# Carduino_328.net
KiCad netlist of a schematic drawn in EAGLE
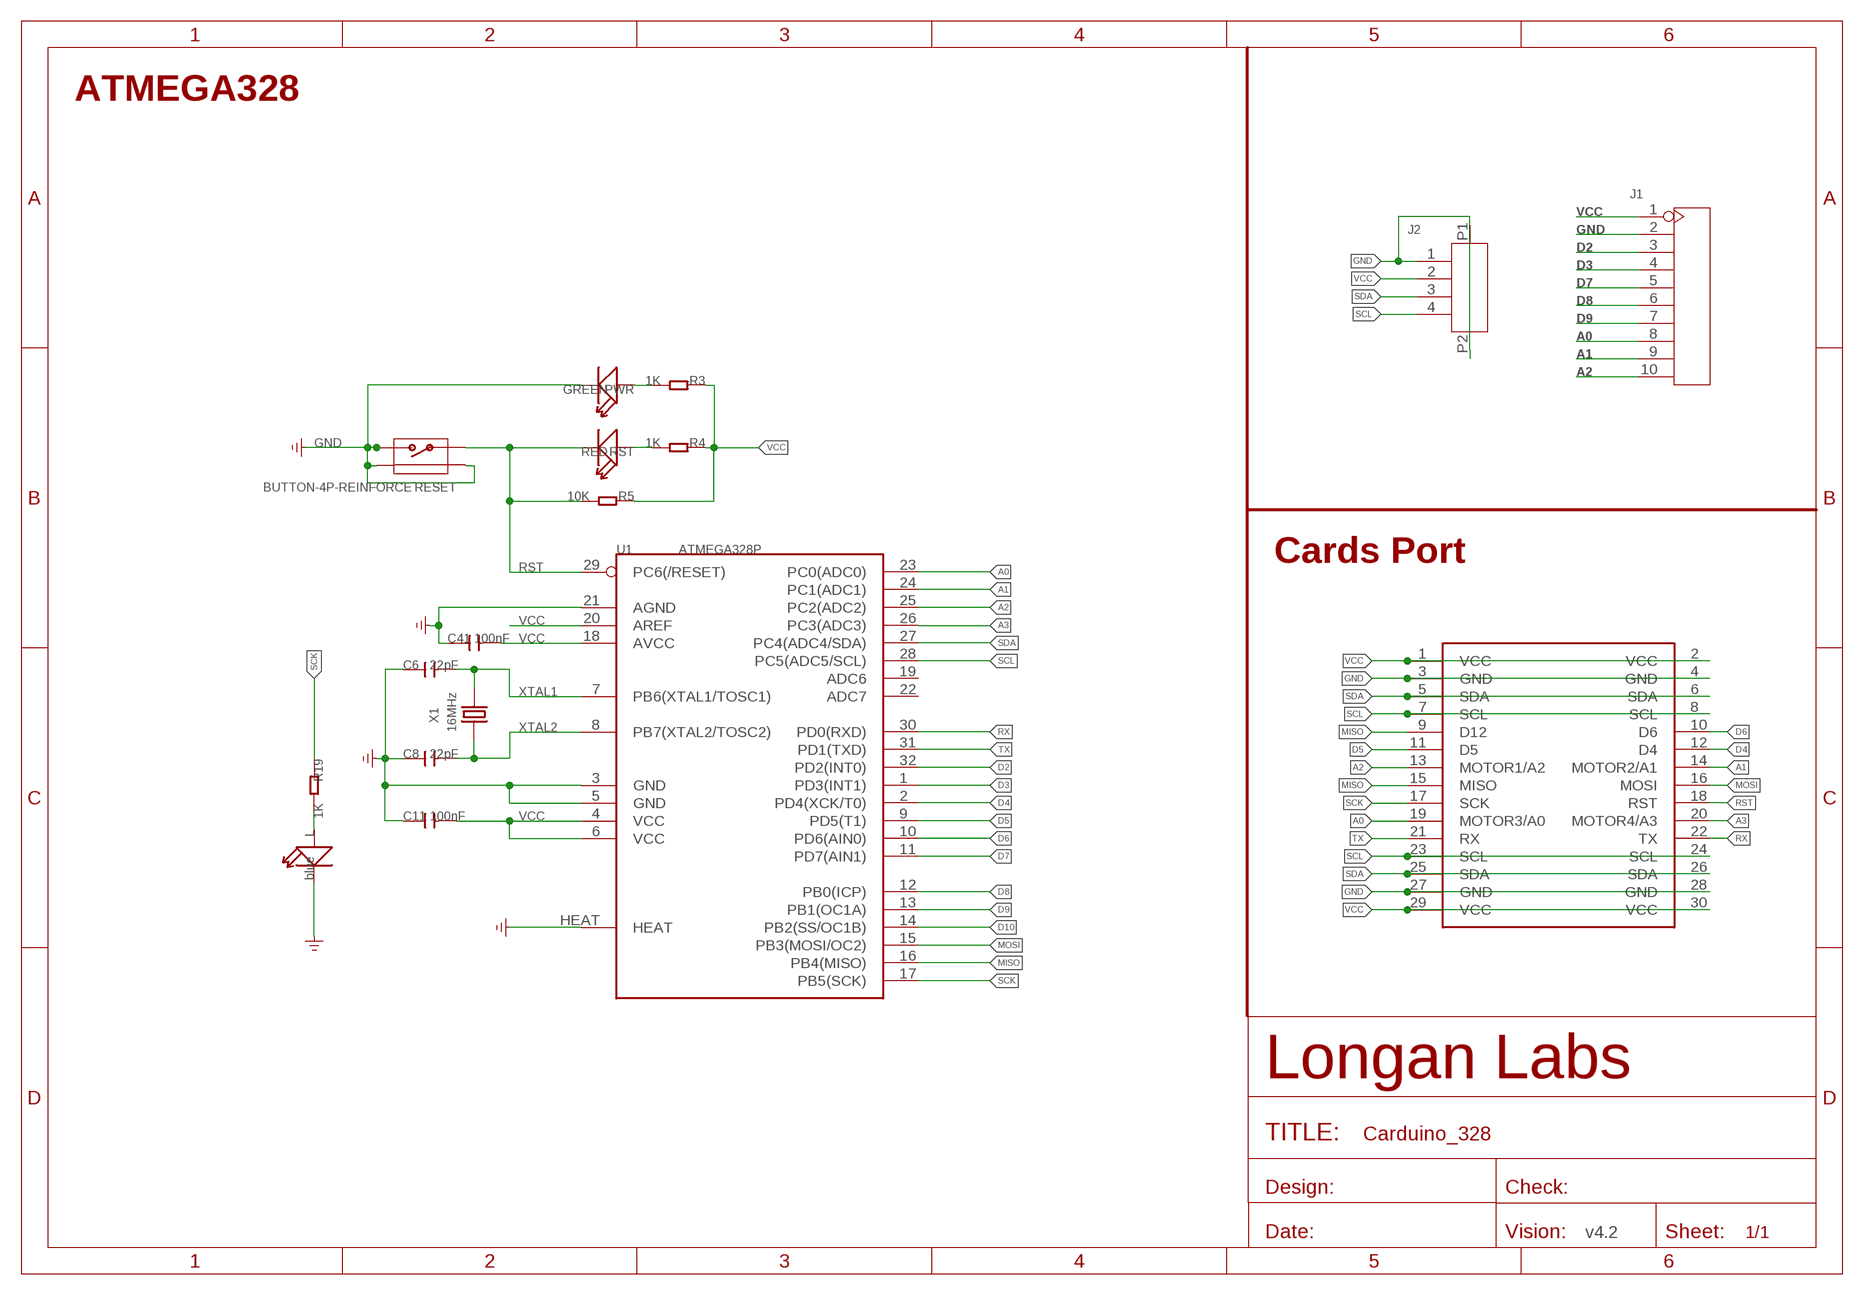
[diagram p0: schematic, sheet 1]

(export (version "E")
  (design (tool "Eeschema 10.0.6"))
  (components
    (comp (ref "C6")
      (value "22pF")
      (footprint "eagle-import:C0603")
      (libsource (lib "eagle-import") (part "C-0603"))
    )
    (comp (ref "C8")
      (value "22pF")
      (footprint "eagle-import:C0603")
      (libsource (lib "eagle-import") (part "C-0603"))
    )
    (comp (ref "C11")
      (value "100nF")
      (footprint "eagle-import:C0603")
      (libsource (lib "eagle-import") (part "C-0603"))
    )
    (comp (ref "C41")
      (value "100nF")
      (footprint "eagle-import:C0603")
      (libsource (lib "eagle-import") (part "C-0603"))
    )
    (comp (ref "J1")
      (value "HEADER-10P-2.54")
      (footprint "eagle-import:H10-2.54")
      (libsource (lib "eagle-import") (part "HEADER-10P-2.54"))
    )
    (comp (ref "J2")
      (value "HEADER-4P-1.0")
      (footprint "eagle-import:4P-1.0-90D")
      (libsource (lib "eagle-import") (part "HEADER-4P-1.0"))
    )
    (comp (ref "L")
      (value "blue")
      (footprint "eagle-import:LED-0603")
      (libsource (lib "eagle-import") (part "LED'0603'"))
    )
    (comp (ref "MOUDLE1")
      (value "MOUDLE-2X15P-MCU'BOARD'")
      (footprint "eagle-import:MOUDLE-2X15P-2.54")
      (libsource (lib "eagle-import") (part "MOUDLE-2X15P-MCU'BOARD'"))
    )
    (comp (ref "PWR")
      (value "GREEN")
      (footprint "eagle-import:LED-0603")
      (libsource (lib "eagle-import") (part "LED'0603'"))
    )
    (comp (ref "R3")
      (value "1K")
      (footprint "eagle-import:R0603")
      (libsource (lib "eagle-import") (part "R-0603"))
    )
    (comp (ref "R4")
      (value "1K")
      (footprint "eagle-import:R0603")
      (libsource (lib "eagle-import") (part "R-0603"))
    )
    (comp (ref "R5")
      (value "10K")
      (footprint "eagle-import:R0603")
      (libsource (lib "eagle-import") (part "R-0603"))
    )
    (comp (ref "R19")
      (value "1K")
      (footprint "eagle-import:R0603")
      (libsource (lib "eagle-import") (part "R-0603"))
    )
    (comp (ref "RESET")
      (value "BUTTON-4P-REINFORCE")
      (footprint "eagle-import:4P-SMD-7X3.5X3.5H")
      (libsource (lib "eagle-import") (part "BUTTON-4P-REINFORCE'TS-1188E'"))
    )
    (comp (ref "RST")
      (value "RED")
      (footprint "eagle-import:LED-0603")
      (libsource (lib "eagle-import") (part "LED'0603'"))
    )
    (comp (ref "U1")
      (value "ATMEGA328P")
      (footprint "eagle-import:MLF32X")
      (libsource (lib "eagle-import") (part "MEGA8"))
    )
    (comp (ref "X1")
      (value "16MHz")
      (footprint "eagle-import:2P-SMD-5X3.2")
      (libsource (lib "eagle-import") (part "CRYSTAL'5032'"))
    )
  )
  (nets
    (net (code "1") (name "/XTAL1") (class "Default")
      (node (ref "C6") (pin "2") (pinfunction "2_2") (pintype "passive"))
      (node (ref "U1") (pin "7") (pinfunction "PB6(XTAL1/TOSC1)_7") (pintype "bidirectional"))
      (node (ref "X1") (pin "2") (pinfunction "2_2") (pintype "passive"))
    )
    (net (code "2") (name "/XTAL2") (class "Default")
      (node (ref "C8") (pin "2") (pinfunction "2_2") (pintype "passive"))
      (node (ref "U1") (pin "8") (pinfunction "PB7(XTAL2/TOSC2)_8") (pintype "bidirectional"))
      (node (ref "X1") (pin "1") (pinfunction "1_1") (pintype "passive"))
    )
    (net (code "3") (name "A0") (class "Default")
      (node (ref "J1") (pin "8") (pinfunction "8_8") (pintype "bidirectional"))
      (node (ref "MOUDLE1") (pin "19") (pinfunction "MOTOR3/A0_19") (pintype "bidirectional"))
      (node (ref "U1") (pin "23") (pinfunction "PC0(ADC0)_23") (pintype "bidirectional"))
    )
    (net (code "4") (name "A1") (class "Default")
      (node (ref "J1") (pin "9") (pinfunction "9_9") (pintype "bidirectional"))
      (node (ref "MOUDLE1") (pin "14") (pinfunction "MOTOR2/A1_14") (pintype "bidirectional"))
      (node (ref "U1") (pin "24") (pinfunction "PC1(ADC1)_24") (pintype "bidirectional"))
    )
    (net (code "5") (name "A2") (class "Default")
      (node (ref "J1") (pin "10") (pinfunction "10_10") (pintype "bidirectional"))
      (node (ref "MOUDLE1") (pin "13") (pinfunction "MOTOR1/A2_13") (pintype "bidirectional"))
      (node (ref "U1") (pin "25") (pinfunction "PC2(ADC2)_25") (pintype "bidirectional"))
    )
    (net (code "6") (name "A3") (class "Default")
      (node (ref "MOUDLE1") (pin "20") (pinfunction "MOTOR4/A3_20") (pintype "bidirectional"))
      (node (ref "U1") (pin "26") (pinfunction "PC3(ADC3)_26") (pintype "bidirectional"))
    )
    (net (code "7") (name "D2") (class "Default")
      (node (ref "J1") (pin "3") (pinfunction "3_3") (pintype "bidirectional"))
      (node (ref "U1") (pin "32") (pinfunction "PD2(INT0)_32") (pintype "bidirectional"))
    )
    (net (code "8") (name "D3") (class "Default")
      (node (ref "J1") (pin "4") (pinfunction "4_4") (pintype "bidirectional"))
      (node (ref "U1") (pin "1") (pinfunction "PD3(INT1)_1") (pintype "bidirectional"))
    )
    (net (code "9") (name "D4") (class "Default")
      (node (ref "MOUDLE1") (pin "12") (pinfunction "D4_12") (pintype "bidirectional"))
      (node (ref "U1") (pin "2") (pinfunction "PD4(XCK/T0)_2") (pintype "bidirectional"))
    )
    (net (code "10") (name "D5") (class "Default")
      (node (ref "MOUDLE1") (pin "11") (pinfunction "D5_11") (pintype "bidirectional"))
      (node (ref "U1") (pin "9") (pinfunction "PD5(T1)_9") (pintype "bidirectional"))
    )
    (net (code "11") (name "D6") (class "Default")
      (node (ref "MOUDLE1") (pin "10") (pinfunction "D6_10") (pintype "bidirectional"))
      (node (ref "U1") (pin "10") (pinfunction "PD6(AIN0)_10") (pintype "bidirectional"))
    )
    (net (code "12") (name "D7") (class "Default")
      (node (ref "J1") (pin "5") (pinfunction "5_5") (pintype "bidirectional"))
      (node (ref "U1") (pin "11") (pinfunction "PD7(AIN1)_11") (pintype "bidirectional"))
    )
    (net (code "13") (name "D8") (class "Default")
      (node (ref "J1") (pin "6") (pinfunction "6_6") (pintype "bidirectional"))
      (node (ref "U1") (pin "12") (pinfunction "PB0(ICP)_12") (pintype "bidirectional"))
    )
    (net (code "14") (name "D9") (class "Default")
      (node (ref "J1") (pin "7") (pinfunction "7_7") (pintype "bidirectional"))
      (node (ref "U1") (pin "13") (pinfunction "PB1(OC1A)_13") (pintype "bidirectional"))
    )
    (net (code "15") (name "D10") (class "Default")
      (node (ref "U1") (pin "14") (pinfunction "PB2(SS/OC1B)_14") (pintype "bidirectional"))
    )
    (net (code "16") (name "GND") (class "Default")
      (node (ref "C11") (pin "1") (pinfunction "1_1") (pintype "passive"))
      (node (ref "C41") (pin "1") (pinfunction "1_1") (pintype "passive"))
      (node (ref "C6") (pin "1") (pinfunction "1_1") (pintype "passive"))
      (node (ref "C8") (pin "1") (pinfunction "1_1") (pintype "passive"))
      (node (ref "J1") (pin "2") (pinfunction "2_2") (pintype "bidirectional"))
      (node (ref "J2") (pin "1") (pinfunction "1_1") (pintype "bidirectional"))
      (node (ref "J2") (pin "P1") (pinfunction "P1_P1") (pintype "bidirectional"))
      (node (ref "J2") (pin "P2") (pinfunction "P2_P2") (pintype "bidirectional"))
      (node (ref "L") (pin "-") (pinfunction "-_-") (pintype "passive"))
      (node (ref "MOUDLE1") (pin "27") (pinfunction "GND_27") (pintype "bidirectional"))
      (node (ref "MOUDLE1") (pin "28") (pinfunction "GND_28") (pintype "bidirectional"))
      (node (ref "MOUDLE1") (pin "3") (pinfunction "GND_3") (pintype "bidirectional"))
      (node (ref "MOUDLE1") (pin "4") (pinfunction "GND_4") (pintype "bidirectional"))
      (node (ref "PWR") (pin "-") (pinfunction "-_-") (pintype "passive"))
      (node (ref "RESET") (pin "2") (pinfunction "2_2") (pintype "bidirectional"))
      (node (ref "RESET") (pin "S1") (pinfunction "S1_S1") (pintype "bidirectional"))
      (node (ref "RESET") (pin "S2") (pinfunction "S2_S2") (pintype "bidirectional"))
      (node (ref "U1") (pin "21") (pinfunction "AGND_21") (pintype "bidirectional"))
      (node (ref "U1") (pin "3") (pinfunction "GND_3") (pintype "bidirectional"))
      (node (ref "U1") (pin "5") (pinfunction "GND_5") (pintype "bidirectional"))
      (node (ref "U1") (pin "HEAT") (pinfunction "HEAT_HEAT") (pintype "bidirectional"))
    )
    (net (code "17") (name "MISO") (class "Default")
      (node (ref "MOUDLE1") (pin "15") (pinfunction "MISO_15") (pintype "bidirectional"))
      (node (ref "MOUDLE1") (pin "9") (pinfunction "D12_9") (pintype "bidirectional"))
      (node (ref "U1") (pin "16") (pinfunction "PB4(MISO)_16") (pintype "bidirectional"))
    )
    (net (code "18") (name "MOSI") (class "Default")
      (node (ref "MOUDLE1") (pin "16") (pinfunction "MOSI_16") (pintype "bidirectional"))
      (node (ref "U1") (pin "15") (pinfunction "PB3(MOSI/OC2)_15") (pintype "bidirectional"))
    )
    (net (code "19") (name "Net-(L-Pad+)") (class "Default")
      (node (ref "L") (pin "+") (pinfunction "+_+") (pintype "passive"))
      (node (ref "R19") (pin "2") (pinfunction "2_2") (pintype "passive"))
    )
    (net (code "20") (name "Net-(PWR-Pad+)") (class "Default")
      (node (ref "PWR") (pin "+") (pinfunction "+_+") (pintype "passive"))
      (node (ref "R3") (pin "2") (pinfunction "2_2") (pintype "passive"))
    )
    (net (code "21") (name "Net-(R4-Pad2)") (class "Default")
      (node (ref "R4") (pin "2") (pinfunction "2_2") (pintype "passive"))
      (node (ref "RST") (pin "+") (pinfunction "+_+") (pintype "passive"))
    )
    (net (code "22") (name "RST") (class "Default")
      (node (ref "MOUDLE1") (pin "18") (pinfunction "RST_18") (pintype "bidirectional"))
      (node (ref "R5") (pin "2") (pinfunction "2_2") (pintype "passive"))
      (node (ref "RESET") (pin "1") (pinfunction "1_1") (pintype "bidirectional"))
      (node (ref "RST") (pin "-") (pinfunction "-_-") (pintype "passive"))
      (node (ref "U1") (pin "29") (pinfunction "PC6(/RESET)_29") (pintype "bidirectional"))
    )
    (net (code "23") (name "RX") (class "Default")
      (node (ref "MOUDLE1") (pin "22") (pinfunction "TX_22") (pintype "bidirectional"))
      (node (ref "U1") (pin "30") (pinfunction "PD0(RXD)_30") (pintype "bidirectional"))
    )
    (net (code "24") (name "SCK") (class "Default")
      (node (ref "MOUDLE1") (pin "17") (pinfunction "SCK_17") (pintype "bidirectional"))
      (node (ref "R19") (pin "1") (pinfunction "1_1") (pintype "passive"))
      (node (ref "U1") (pin "17") (pinfunction "PB5(SCK)_17") (pintype "bidirectional"))
    )
    (net (code "25") (name "SCL") (class "Default")
      (node (ref "J2") (pin "4") (pinfunction "4_4") (pintype "bidirectional"))
      (node (ref "MOUDLE1") (pin "23") (pinfunction "SCL_23") (pintype "bidirectional"))
      (node (ref "MOUDLE1") (pin "24") (pinfunction "SCL_24") (pintype "bidirectional"))
      (node (ref "MOUDLE1") (pin "7") (pinfunction "SCL_7") (pintype "bidirectional"))
      (node (ref "MOUDLE1") (pin "8") (pinfunction "SCL_8") (pintype "bidirectional"))
      (node (ref "U1") (pin "28") (pinfunction "PC5(ADC5/SCL)_28") (pintype "bidirectional"))
    )
    (net (code "26") (name "SDA") (class "Default")
      (node (ref "J2") (pin "3") (pinfunction "3_3") (pintype "bidirectional"))
      (node (ref "MOUDLE1") (pin "25") (pinfunction "SDA_25") (pintype "bidirectional"))
      (node (ref "MOUDLE1") (pin "26") (pinfunction "SDA_26") (pintype "bidirectional"))
      (node (ref "MOUDLE1") (pin "5") (pinfunction "SDA_5") (pintype "bidirectional"))
      (node (ref "MOUDLE1") (pin "6") (pinfunction "SDA_6") (pintype "bidirectional"))
      (node (ref "U1") (pin "27") (pinfunction "PC4(ADC4/SDA)_27") (pintype "bidirectional"))
    )
    (net (code "27") (name "TX") (class "Default")
      (node (ref "MOUDLE1") (pin "21") (pinfunction "RX_21") (pintype "bidirectional"))
      (node (ref "U1") (pin "31") (pinfunction "PD1(TXD)_31") (pintype "bidirectional"))
    )
    (net (code "28") (name "VCC") (class "Default")
      (node (ref "C11") (pin "2") (pinfunction "2_2") (pintype "passive"))
      (node (ref "C41") (pin "2") (pinfunction "2_2") (pintype "passive"))
      (node (ref "J1") (pin "1") (pinfunction "1_1") (pintype "bidirectional"))
      (node (ref "J2") (pin "2") (pinfunction "2_2") (pintype "bidirectional"))
      (node (ref "MOUDLE1") (pin "1") (pinfunction "VCC_1") (pintype "bidirectional"))
      (node (ref "MOUDLE1") (pin "2") (pinfunction "VCC_2") (pintype "bidirectional"))
      (node (ref "MOUDLE1") (pin "29") (pinfunction "VCC_29") (pintype "bidirectional"))
      (node (ref "MOUDLE1") (pin "30") (pinfunction "VCC_30") (pintype "bidirectional"))
      (node (ref "R3") (pin "1") (pinfunction "1_1") (pintype "passive"))
      (node (ref "R4") (pin "1") (pinfunction "1_1") (pintype "passive"))
      (node (ref "R5") (pin "1") (pinfunction "1_1") (pintype "passive"))
      (node (ref "U1") (pin "18") (pinfunction "AVCC_18") (pintype "bidirectional"))
      (node (ref "U1") (pin "20") (pinfunction "AREF_20") (pintype "bidirectional"))
      (node (ref "U1") (pin "4") (pinfunction "VCC_4") (pintype "bidirectional"))
      (node (ref "U1") (pin "6") (pinfunction "VCC_6") (pintype "bidirectional"))
    )
    (net (code "29") (name "unconnected-(U1-ADC6-Pad19)") (class "Default")
      (node (ref "U1") (pin "19") (pinfunction "ADC6_19") (pintype "bidirectional"))
    )
    (net (code "30") (name "unconnected-(U1-ADC7-Pad22)") (class "Default")
      (node (ref "U1") (pin "22") (pinfunction "ADC7_22") (pintype "bidirectional"))
    )
  )
)
